# chunkycopter-v2.net
KiCad netlist of a schematic drawn in EAGLE
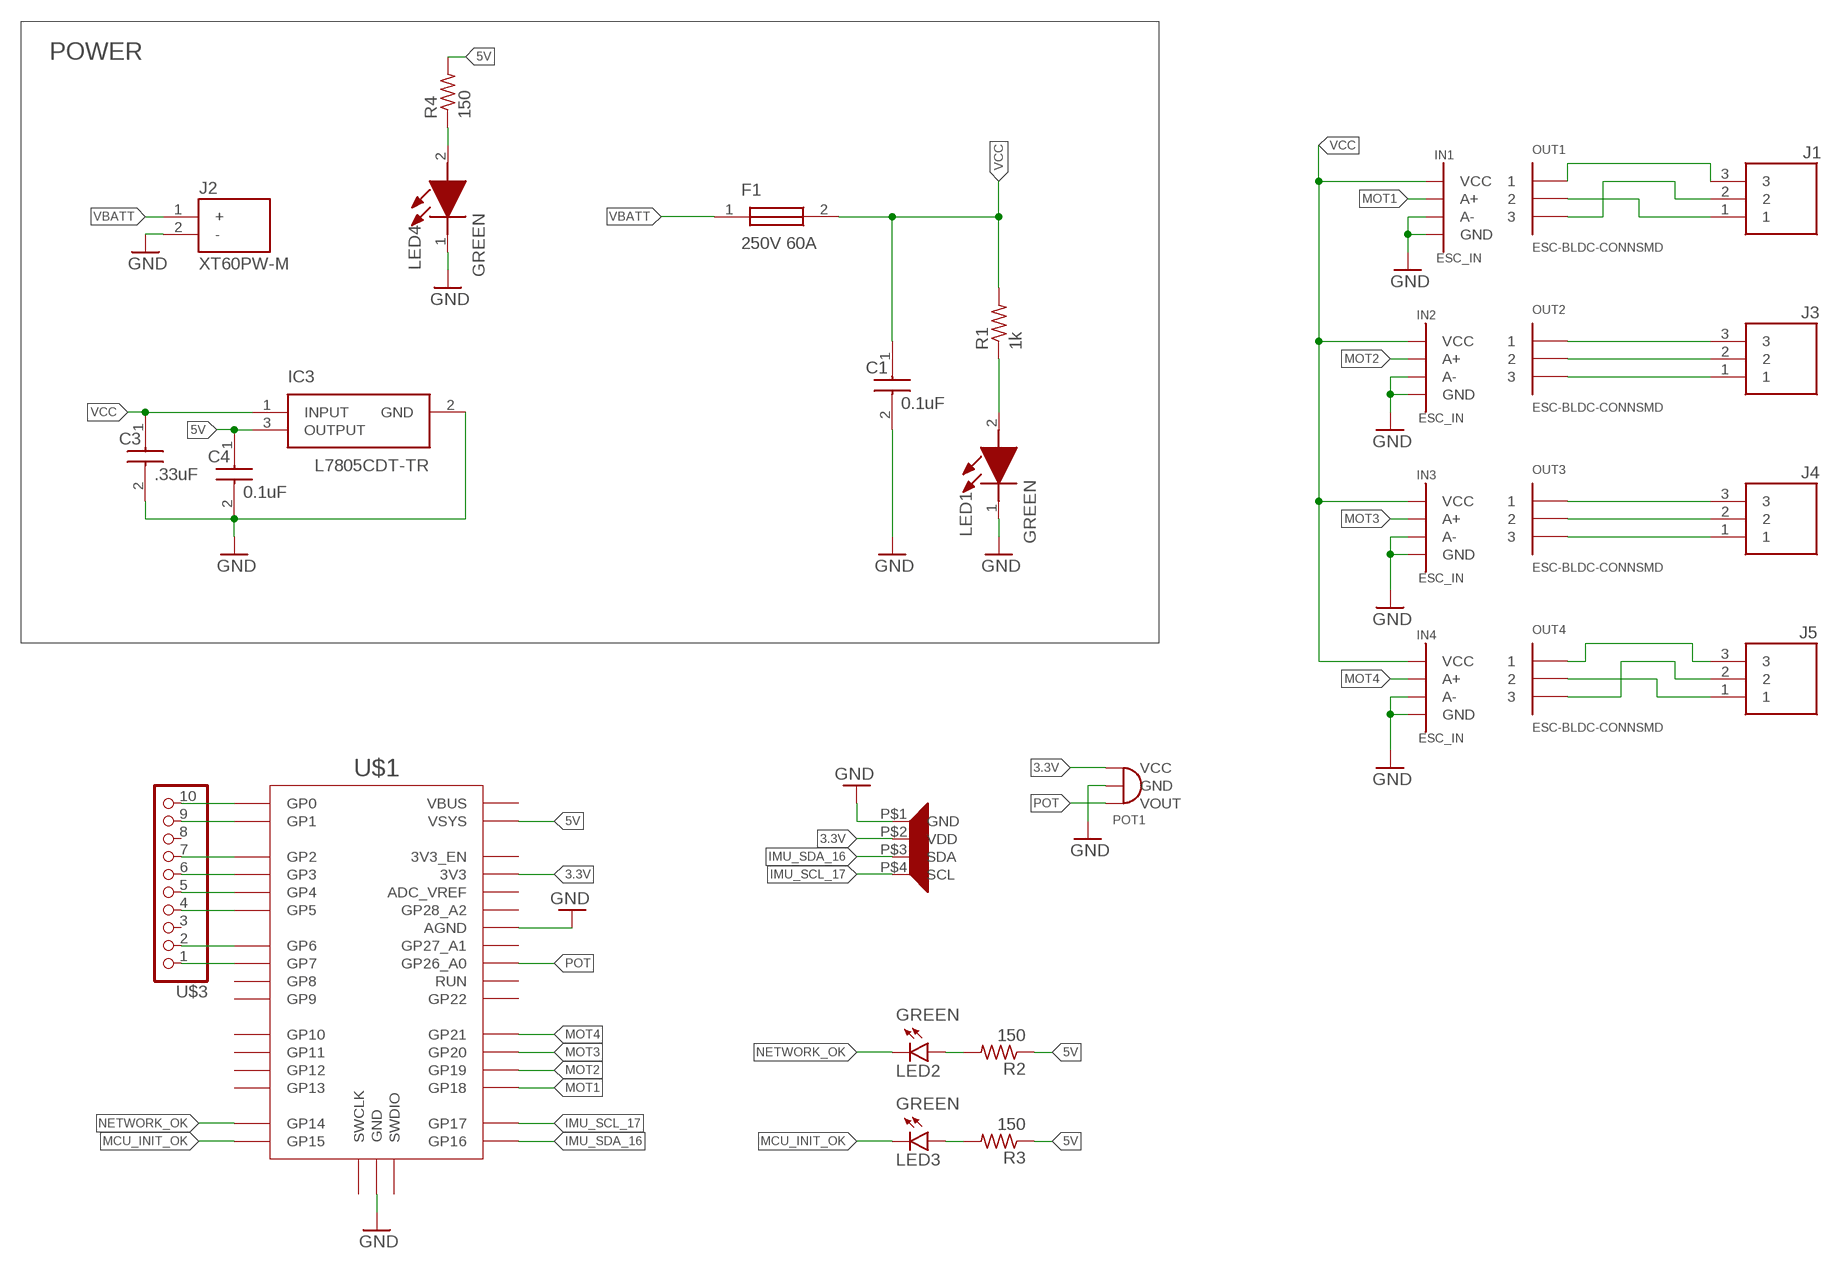
[diagram p0: schematic, sheet 1]

(export (version "E")
  (design (tool "Eeschema 10.0.6"))
  (components
    (comp (ref "C1")
      (value "0.1uF")
      (footprint "eagle-import:C0805")
      (fields
        (field (name "MANUFACTURER_PART_NUMBER") "C0805C104K5RACTU")
        (field (name "MOUSER_PART_NUMBER") "80-C0805C104K5R")
      )
      (libsource (lib "eagle-import") (part "C0805C104K5RACTU"))
    )
    (comp (ref "C3")
      (value ".33uF")
      (footprint "eagle-import:C0805")
      (fields
        (field (name "MANUFACTURER_PART_NUMBER") "C0805C334K5RACTU")
        (field (name "MOUSER_PART_NUMBER") "80-C0805C334K5R")
      )
      (libsource (lib "eagle-import") (part "C0805C334K5RACTU"))
    )
    (comp (ref "C4")
      (value "0.1uF")
      (footprint "eagle-import:C0805")
      (fields
        (field (name "MANUFACTURER_PART_NUMBER") "C0805C104K5RACTU")
        (field (name "MOUSER_PART_NUMBER") "80-C0805C104K5R")
      )
      (libsource (lib "eagle-import") (part "C0805C104K5RACTU"))
    )
    (comp (ref "F1")
      (value "250V 60A")
      (footprint "eagle-import:0456060DRSDE")
      (fields
        (field (name "MANUFACTURER_PART_NUMBER") "0456060.DRSDE")
        (field (name "MOUSER_PART_NUMBER") "576-0456060.DRSDE")
      )
      (libsource (lib "eagle-import") (part "0456060.DRSDE"))
    )
    (comp (ref "IC3")
      (value "L7805CDT-TR")
      (footprint "eagle-import:L7805CDTTR")
      (fields (field (name "MOUSER_PART_NUMBER") "511-L7805CDT-TR"))
      (libsource (lib "eagle-import") (part "L7805CDT-TR"))
    )
    (comp (ref "IN1")
      (value "ESC_IN")
      (footprint "eagle-import:ESC-INPUT")
      (libsource (lib "eagle-import") (part "ESC_IN"))
    )
    (comp (ref "IN2")
      (value "ESC_IN")
      (footprint "eagle-import:ESC-INPUT")
      (libsource (lib "eagle-import") (part "ESC_IN"))
    )
    (comp (ref "IN3")
      (value "ESC_IN")
      (footprint "eagle-import:ESC-INPUT")
      (libsource (lib "eagle-import") (part "ESC_IN"))
    )
    (comp (ref "IN4")
      (value "ESC_IN")
      (footprint "eagle-import:ESC-INPUT")
      (libsource (lib "eagle-import") (part "ESC_IN"))
    )
    (comp (ref "J1")
      (value "MOLEX-CONN-39-30-3037")
      (footprint "eagle-import:39303037")
      (fields
        (field (name "MANUFACTURER_PART_NUMBER") "39-30-3037")
        (field (name "MOUSER_PART_NUMBER") "538-39-30-3037")
      )
      (libsource (lib "eagle-import") (part "MOLEX-CONN-39-30-3037"))
    )
    (comp (ref "J2")
      (value "XT60PW-M")
      (footprint "eagle-import:AMASS_XT60PW-M")
      (fields (field (name "MF") "AMASS"))
      (libsource (lib "eagle-import") (part "XT60PW-M"))
    )
    (comp (ref "J3")
      (value "MOLEX-CONN-39-30-3037")
      (footprint "eagle-import:39303037")
      (fields
        (field (name "MANUFACTURER_PART_NUMBER") "39-30-3037")
        (field (name "MOUSER_PART_NUMBER") "538-39-30-3037")
      )
      (libsource (lib "eagle-import") (part "MOLEX-CONN-39-30-3037"))
    )
    (comp (ref "J4")
      (value "MOLEX-CONN-39-30-3037")
      (footprint "eagle-import:39303037")
      (fields
        (field (name "MANUFACTURER_PART_NUMBER") "39-30-3037")
        (field (name "MOUSER_PART_NUMBER") "538-39-30-3037")
      )
      (libsource (lib "eagle-import") (part "MOLEX-CONN-39-30-3037"))
    )
    (comp (ref "J5")
      (value "MOLEX-CONN-39-30-3037")
      (footprint "eagle-import:39303037")
      (fields
        (field (name "MANUFACTURER_PART_NUMBER") "39-30-3037")
        (field (name "MOUSER_PART_NUMBER") "538-39-30-3037")
      )
      (libsource (lib "eagle-import") (part "MOLEX-CONN-39-30-3037"))
    )
    (comp (ref "LED1")
      (value "GREEN")
      (footprint "eagle-import:SML012ENTT86")
      (fields
        (field (name "MANUFACTURER_PART_NUMBER") "SML012ENTT86")
        (field (name "MOUSER_PART_NUMBER") "755-SML012ENTT86")
      )
      (libsource (lib "eagle-import") (part "SML012ENTT86"))
    )
    (comp (ref "LED2")
      (value "GREEN")
      (footprint "eagle-import:CHIPLED_0603")
      (libsource (lib "eagle-import") (part "LEDCHIPLED_0603"))
    )
    (comp (ref "LED3")
      (value "GREEN")
      (footprint "eagle-import:CHIPLED_0603")
      (libsource (lib "eagle-import") (part "LEDCHIPLED_0603"))
    )
    (comp (ref "LED4")
      (value "GREEN")
      (footprint "eagle-import:SML012ENTT86")
      (fields
        (field (name "MANUFACTURER_PART_NUMBER") "SML012ENTT86")
        (field (name "MOUSER_PART_NUMBER") "755-SML012ENTT86")
      )
      (libsource (lib "eagle-import") (part "SML012ENTT86"))
    )
    (comp (ref "OUT1")
      (value "ESC-BLDC-CONNSMD")
      (footprint "eagle-import:ESC-OUT")
      (libsource (lib "eagle-import") (part "ESC-BLDC-CONNSMD"))
    )
    (comp (ref "OUT2")
      (value "ESC-BLDC-CONNSMD")
      (footprint "eagle-import:ESC-OUT")
      (libsource (lib "eagle-import") (part "ESC-BLDC-CONNSMD"))
    )
    (comp (ref "OUT3")
      (value "ESC-BLDC-CONNSMD")
      (footprint "eagle-import:ESC-OUT")
      (libsource (lib "eagle-import") (part "ESC-BLDC-CONNSMD"))
    )
    (comp (ref "OUT4")
      (value "ESC-BLDC-CONNSMD")
      (footprint "eagle-import:ESC-OUT")
      (libsource (lib "eagle-import") (part "ESC-BLDC-CONNSMD"))
    )
    (comp (ref "POT1")
      (value "POT-CONN")
      (footprint "eagle-import:POT")
      (libsource (lib "eagle-import") (part "POT-CONN"))
    )
    (comp (ref "R1")
      (value "1k")
      (footprint "eagle-import:R0805")
      (libsource (lib "eagle-import") (part "R-US_R0805"))
    )
    (comp (ref "R2")
      (value "150")
      (footprint "eagle-import:R0805")
      (libsource (lib "eagle-import") (part "R-US_R0805"))
    )
    (comp (ref "R3")
      (value "150")
      (footprint "eagle-import:R0805")
      (libsource (lib "eagle-import") (part "R-US_R0805"))
    )
    (comp (ref "R4")
      (value "150")
      (footprint "eagle-import:R0805")
      (libsource (lib "eagle-import") (part "R-US_R0805"))
    )
    (comp (ref "U$1")
      (value "RPI_PICO-TH")
      (footprint "eagle-import:RPI_PICO_TH")
      (libsource (lib "eagle-import") (part "RPI_PICO-TH"))
    )
    (comp (ref "U$2")
      (value "LSM9DS1_IMU")
      (footprint "eagle-import:LSM9DS1_IMU")
      (libsource (lib "eagle-import") (part "LSM9DS1_IMU"))
    )
    (comp (ref "U$3")
      (value "PINHD-1X10")
      (footprint "eagle-import:1X10-BIG")
      (libsource (lib "eagle-import") (part "PINHD-1X10"))
    )
  )
  (nets
    (net (code "1") (name "3.3V") (class "Default")
      (node (ref "POT1") (pin "P_VCC") (pinfunction "VCC_P_VCC") (pintype "bidirectional"))
      (node (ref "U$1") (pin "3V3") (pinfunction "3V3_3V3") (pintype "bidirectional"))
      (node (ref "U$2") (pin "P$2") (pinfunction "VDD_P$2") (pintype "bidirectional"))
    )
    (net (code "2") (name "5V") (class "Default")
      (node (ref "C4") (pin "1") (pinfunction "1_1") (pintype "bidirectional"))
      (node (ref "IC3") (pin "3") (pinfunction "OUTPUT_3") (pintype "bidirectional"))
      (node (ref "R2") (pin "1") (pinfunction "1_1") (pintype "passive"))
      (node (ref "R3") (pin "1") (pinfunction "1_1") (pintype "passive"))
      (node (ref "R4") (pin "2") (pinfunction "2_2") (pintype "passive"))
      (node (ref "U$1") (pin "VSYS") (pinfunction "VSYS_VSYS") (pintype "bidirectional"))
    )
    (net (code "3") (name "GND") (class "Default")
      (node (ref "C1") (pin "2") (pinfunction "2_2") (pintype "bidirectional"))
      (node (ref "C3") (pin "2") (pinfunction "2_2") (pintype "bidirectional"))
      (node (ref "C4") (pin "2") (pinfunction "2_2") (pintype "bidirectional"))
      (node (ref "IC3") (pin "2") (pinfunction "GND_2") (pintype "bidirectional"))
      (node (ref "IN1") (pin "A-") (pinfunction "A-_A-") (pintype "bidirectional"))
      (node (ref "IN1") (pin "GND") (pinfunction "GND_GND") (pintype "bidirectional"))
      (node (ref "IN2") (pin "A-") (pinfunction "A-_A-") (pintype "bidirectional"))
      (node (ref "IN2") (pin "GND") (pinfunction "GND_GND") (pintype "bidirectional"))
      (node (ref "IN3") (pin "A-") (pinfunction "A-_A-") (pintype "bidirectional"))
      (node (ref "IN3") (pin "GND") (pinfunction "GND_GND") (pintype "bidirectional"))
      (node (ref "IN4") (pin "A-") (pinfunction "A-_A-") (pintype "bidirectional"))
      (node (ref "IN4") (pin "GND") (pinfunction "GND_GND") (pintype "bidirectional"))
      (node (ref "J2") (pin "2") (pinfunction "-_2") (pintype "passive"))
      (node (ref "LED1") (pin "1") (pinfunction "K_1") (pintype "bidirectional"))
      (node (ref "LED4") (pin "1") (pinfunction "K_1") (pintype "bidirectional"))
      (node (ref "POT1") (pin "P_GND") (pinfunction "GND_P_GND") (pintype "bidirectional"))
      (node (ref "U$1") (pin "AGND") (pinfunction "AGND_AGND") (pintype "bidirectional"))
      (node (ref "U$1") (pin "GND@1") (pinfunction "GND_GND@1") (pintype "bidirectional"))
      (node (ref "U$1") (pin "GND@2") (pinfunction "GND_GND@2") (pintype "bidirectional"))
      (node (ref "U$1") (pin "GND@3") (pinfunction "GND_GND@3") (pintype "bidirectional"))
      (node (ref "U$1") (pin "GND@4") (pinfunction "GND_GND@4") (pintype "bidirectional"))
      (node (ref "U$1") (pin "GND@5") (pinfunction "GND_GND@5") (pintype "bidirectional"))
      (node (ref "U$1") (pin "GND@6") (pinfunction "GND_GND@6") (pintype "bidirectional"))
      (node (ref "U$1") (pin "GND@7") (pinfunction "GND_GND@7") (pintype "bidirectional"))
      (node (ref "U$1") (pin "GND@8") (pinfunction "GND_GND@8") (pintype "bidirectional"))
      (node (ref "U$2") (pin "P$1") (pinfunction "GND_P$1") (pintype "bidirectional"))
    )
    (net (code "4") (name "IMU_SCL_17") (class "Default")
      (node (ref "U$1") (pin "GP17") (pinfunction "GP17_GP17") (pintype "bidirectional"))
      (node (ref "U$2") (pin "P$4") (pinfunction "SCL_P$4") (pintype "bidirectional"))
    )
    (net (code "5") (name "IMU_SDA_16") (class "Default")
      (node (ref "U$1") (pin "GP16") (pinfunction "GP16_GP16") (pintype "bidirectional"))
      (node (ref "U$2") (pin "P$3") (pinfunction "SDA_P$3") (pintype "bidirectional"))
    )
    (net (code "6") (name "MCU_INIT_OK") (class "Default")
      (node (ref "LED3") (pin "C") (pinfunction "C_C") (pintype "passive"))
      (node (ref "U$1") (pin "GP15") (pinfunction "GP15_GP15") (pintype "bidirectional"))
    )
    (net (code "7") (name "MOT1") (class "Default")
      (node (ref "IN1") (pin "A+") (pinfunction "A+_A+") (pintype "bidirectional"))
      (node (ref "U$1") (pin "GP18") (pinfunction "GP18_GP18") (pintype "bidirectional"))
    )
    (net (code "8") (name "MOT2") (class "Default")
      (node (ref "IN2") (pin "A+") (pinfunction "A+_A+") (pintype "bidirectional"))
      (node (ref "U$1") (pin "GP19") (pinfunction "GP19_GP19") (pintype "bidirectional"))
    )
    (net (code "9") (name "MOT3") (class "Default")
      (node (ref "IN3") (pin "A+") (pinfunction "A+_A+") (pintype "bidirectional"))
      (node (ref "U$1") (pin "GP20") (pinfunction "GP20_GP20") (pintype "bidirectional"))
    )
    (net (code "10") (name "MOT4") (class "Default")
      (node (ref "IN4") (pin "A+") (pinfunction "A+_A+") (pintype "bidirectional"))
      (node (ref "U$1") (pin "GP21") (pinfunction "GP21_GP21") (pintype "bidirectional"))
    )
    (net (code "11") (name "NETWORK_OK") (class "Default")
      (node (ref "LED2") (pin "C") (pinfunction "C_C") (pintype "passive"))
      (node (ref "U$1") (pin "GP14") (pinfunction "GP14_GP14") (pintype "bidirectional"))
    )
    (net (code "12") (name "Net-(J1-Pad1)") (class "Default")
      (node (ref "J1") (pin "1") (pinfunction "1_1") (pintype "bidirectional"))
      (node (ref "OUT1") (pin "2") (pinfunction "2_2") (pintype "bidirectional"))
    )
    (net (code "13") (name "Net-(J1-Pad2)") (class "Default")
      (node (ref "J1") (pin "2") (pinfunction "2_2") (pintype "bidirectional"))
      (node (ref "OUT1") (pin "3") (pinfunction "3_3") (pintype "bidirectional"))
    )
    (net (code "14") (name "Net-(J1-Pad3)") (class "Default")
      (node (ref "J1") (pin "3") (pinfunction "3_3") (pintype "bidirectional"))
      (node (ref "OUT1") (pin "1") (pinfunction "1_1") (pintype "bidirectional"))
    )
    (net (code "15") (name "Net-(J3-Pad1)") (class "Default")
      (node (ref "J3") (pin "1") (pinfunction "1_1") (pintype "bidirectional"))
      (node (ref "OUT2") (pin "3") (pinfunction "3_3") (pintype "bidirectional"))
    )
    (net (code "16") (name "Net-(J3-Pad2)") (class "Default")
      (node (ref "J3") (pin "2") (pinfunction "2_2") (pintype "bidirectional"))
      (node (ref "OUT2") (pin "2") (pinfunction "2_2") (pintype "bidirectional"))
    )
    (net (code "17") (name "Net-(J3-Pad3)") (class "Default")
      (node (ref "J3") (pin "3") (pinfunction "3_3") (pintype "bidirectional"))
      (node (ref "OUT2") (pin "1") (pinfunction "1_1") (pintype "bidirectional"))
    )
    (net (code "18") (name "Net-(J4-Pad1)") (class "Default")
      (node (ref "J4") (pin "1") (pinfunction "1_1") (pintype "bidirectional"))
      (node (ref "OUT3") (pin "3") (pinfunction "3_3") (pintype "bidirectional"))
    )
    (net (code "19") (name "Net-(J4-Pad2)") (class "Default")
      (node (ref "J4") (pin "2") (pinfunction "2_2") (pintype "bidirectional"))
      (node (ref "OUT3") (pin "2") (pinfunction "2_2") (pintype "bidirectional"))
    )
    (net (code "20") (name "Net-(J4-Pad3)") (class "Default")
      (node (ref "J4") (pin "3") (pinfunction "3_3") (pintype "bidirectional"))
      (node (ref "OUT3") (pin "1") (pinfunction "1_1") (pintype "bidirectional"))
    )
    (net (code "21") (name "Net-(J5-Pad1)") (class "Default")
      (node (ref "J5") (pin "1") (pinfunction "1_1") (pintype "bidirectional"))
      (node (ref "OUT4") (pin "2") (pinfunction "2_2") (pintype "bidirectional"))
    )
    (net (code "22") (name "Net-(J5-Pad2)") (class "Default")
      (node (ref "J5") (pin "2") (pinfunction "2_2") (pintype "bidirectional"))
      (node (ref "OUT4") (pin "3") (pinfunction "3_3") (pintype "bidirectional"))
    )
    (net (code "23") (name "Net-(J5-Pad3)") (class "Default")
      (node (ref "J5") (pin "3") (pinfunction "3_3") (pintype "bidirectional"))
      (node (ref "OUT4") (pin "1") (pinfunction "1_1") (pintype "bidirectional"))
    )
    (net (code "24") (name "Net-(LED1-A)") (class "Default")
      (node (ref "LED1") (pin "2") (pinfunction "A_2") (pintype "bidirectional"))
      (node (ref "R1") (pin "1") (pinfunction "1_1") (pintype "passive"))
    )
    (net (code "25") (name "Net-(LED2-PadA)") (class "Default")
      (node (ref "LED2") (pin "A") (pinfunction "A_A") (pintype "passive"))
      (node (ref "R2") (pin "2") (pinfunction "2_2") (pintype "passive"))
    )
    (net (code "26") (name "Net-(LED3-PadA)") (class "Default")
      (node (ref "LED3") (pin "A") (pinfunction "A_A") (pintype "passive"))
      (node (ref "R3") (pin "2") (pinfunction "2_2") (pintype "passive"))
    )
    (net (code "27") (name "Net-(LED4-A)") (class "Default")
      (node (ref "LED4") (pin "2") (pinfunction "A_2") (pintype "bidirectional"))
      (node (ref "R4") (pin "1") (pinfunction "1_1") (pintype "passive"))
    )
    (net (code "28") (name "Net-(U$1-PadGP0)") (class "Default")
      (node (ref "U$1") (pin "GP0") (pinfunction "GP0_GP0") (pintype "bidirectional"))
      (node (ref "U$3") (pin "10") (pinfunction "10_10") (pintype "passive"))
    )
    (net (code "29") (name "Net-(U$1-PadGP1)") (class "Default")
      (node (ref "U$1") (pin "GP1") (pinfunction "GP1_GP1") (pintype "bidirectional"))
      (node (ref "U$3") (pin "9") (pinfunction "9_9") (pintype "passive"))
    )
    (net (code "30") (name "Net-(U$1-PadGP2)") (class "Default")
      (node (ref "U$1") (pin "GP2") (pinfunction "GP2_GP2") (pintype "bidirectional"))
      (node (ref "U$3") (pin "7") (pinfunction "7_7") (pintype "passive"))
    )
    (net (code "31") (name "Net-(U$1-PadGP3)") (class "Default")
      (node (ref "U$1") (pin "GP3") (pinfunction "GP3_GP3") (pintype "bidirectional"))
      (node (ref "U$3") (pin "6") (pinfunction "6_6") (pintype "passive"))
    )
    (net (code "32") (name "Net-(U$1-PadGP4)") (class "Default")
      (node (ref "U$1") (pin "GP4") (pinfunction "GP4_GP4") (pintype "bidirectional"))
      (node (ref "U$3") (pin "5") (pinfunction "5_5") (pintype "passive"))
    )
    (net (code "33") (name "Net-(U$1-PadGP5)") (class "Default")
      (node (ref "U$1") (pin "GP5") (pinfunction "GP5_GP5") (pintype "bidirectional"))
      (node (ref "U$3") (pin "4") (pinfunction "4_4") (pintype "passive"))
    )
    (net (code "34") (name "Net-(U$1-PadGP6)") (class "Default")
      (node (ref "U$1") (pin "GP6") (pinfunction "GP6_GP6") (pintype "bidirectional"))
      (node (ref "U$3") (pin "2") (pinfunction "2_2") (pintype "passive"))
    )
    (net (code "35") (name "Net-(U$1-PadGP7)") (class "Default")
      (node (ref "U$1") (pin "GP7") (pinfunction "GP7_GP7") (pintype "bidirectional"))
      (node (ref "U$3") (pin "1") (pinfunction "1_1") (pintype "passive"))
    )
    (net (code "36") (name "POT") (class "Default")
      (node (ref "POT1") (pin "P_VOUT") (pinfunction "VOUT_P_VOUT") (pintype "bidirectional"))
      (node (ref "U$1") (pin "GP26_A0") (pinfunction "GP26_A0_GP26_A0") (pintype "bidirectional"))
    )
    (net (code "37") (name "VBATT") (class "Default")
      (node (ref "F1") (pin "1") (pinfunction "1_1") (pintype "bidirectional"))
      (node (ref "J2") (pin "1") (pinfunction "+_1") (pintype "passive"))
    )
    (net (code "38") (name "VCC") (class "Default")
      (node (ref "C1") (pin "1") (pinfunction "1_1") (pintype "bidirectional"))
      (node (ref "C3") (pin "1") (pinfunction "1_1") (pintype "bidirectional"))
      (node (ref "F1") (pin "2") (pinfunction "2_2") (pintype "bidirectional"))
      (node (ref "IC3") (pin "1") (pinfunction "INPUT_1") (pintype "bidirectional"))
      (node (ref "IN1") (pin "VCC") (pinfunction "VCC_VCC") (pintype "bidirectional"))
      (node (ref "IN2") (pin "VCC") (pinfunction "VCC_VCC") (pintype "bidirectional"))
      (node (ref "IN3") (pin "VCC") (pinfunction "VCC_VCC") (pintype "bidirectional"))
      (node (ref "IN4") (pin "VCC") (pinfunction "VCC_VCC") (pintype "bidirectional"))
      (node (ref "R1") (pin "2") (pinfunction "2_2") (pintype "passive"))
    )
    (net (code "39") (name "unconnected-(U$1-Pad3V3_EN)") (class "Default")
      (node (ref "U$1") (pin "3V3_EN") (pinfunction "3V3_EN_3V3_EN") (pintype "bidirectional"))
    )
    (net (code "40") (name "unconnected-(U$1-PadADC_VREF)") (class "Default")
      (node (ref "U$1") (pin "ADC_VREF") (pinfunction "ADC_VREF_ADC_VREF") (pintype "bidirectional"))
    )
    (net (code "41") (name "unconnected-(U$1-PadGP8)") (class "Default")
      (node (ref "U$1") (pin "GP8") (pinfunction "GP8_GP8") (pintype "bidirectional"))
    )
    (net (code "42") (name "unconnected-(U$1-PadGP9)") (class "Default")
      (node (ref "U$1") (pin "GP9") (pinfunction "GP9_GP9") (pintype "bidirectional"))
    )
    (net (code "43") (name "unconnected-(U$1-PadGP10)") (class "Default")
      (node (ref "U$1") (pin "GP10") (pinfunction "GP10_GP10") (pintype "bidirectional"))
    )
    (net (code "44") (name "unconnected-(U$1-PadGP11)") (class "Default")
      (node (ref "U$1") (pin "GP11") (pinfunction "GP11_GP11") (pintype "bidirectional"))
    )
    (net (code "45") (name "unconnected-(U$1-PadGP12)") (class "Default")
      (node (ref "U$1") (pin "GP12") (pinfunction "GP12_GP12") (pintype "bidirectional"))
    )
    (net (code "46") (name "unconnected-(U$1-PadGP13)") (class "Default")
      (node (ref "U$1") (pin "GP13") (pinfunction "GP13_GP13") (pintype "bidirectional"))
    )
    (net (code "47") (name "unconnected-(U$1-PadGP22)") (class "Default")
      (node (ref "U$1") (pin "GP22") (pinfunction "GP22_GP22") (pintype "bidirectional"))
    )
    (net (code "48") (name "unconnected-(U$1-PadGP27_A1)") (class "Default")
      (node (ref "U$1") (pin "GP27_A1") (pinfunction "GP27_A1_GP27_A1") (pintype "bidirectional"))
    )
    (net (code "49") (name "unconnected-(U$1-PadGP28_A2)") (class "Default")
      (node (ref "U$1") (pin "GP28_A2") (pinfunction "GP28_A2_GP28_A2") (pintype "bidirectional"))
    )
    (net (code "50") (name "unconnected-(U$1-PadRUN)") (class "Default")
      (node (ref "U$1") (pin "RUN") (pinfunction "RUN_RUN") (pintype "bidirectional"))
    )
    (net (code "51") (name "unconnected-(U$1-PadSWCLK)") (class "Default")
      (node (ref "U$1") (pin "SWCLK") (pinfunction "SWCLK_SWCLK") (pintype "bidirectional"))
    )
    (net (code "52") (name "unconnected-(U$1-PadSWDIO)") (class "Default")
      (node (ref "U$1") (pin "SWDIO") (pinfunction "SWDIO_SWDIO") (pintype "bidirectional"))
    )
    (net (code "53") (name "unconnected-(U$1-PadVBUS)") (class "Default")
      (node (ref "U$1") (pin "VBUS") (pinfunction "VBUS_VBUS") (pintype "bidirectional"))
    )
    (net (code "54") (name "unconnected-(U$3-Pad3)") (class "Default")
      (node (ref "U$3") (pin "3") (pinfunction "3_3") (pintype "passive"))
    )
    (net (code "55") (name "unconnected-(U$3-Pad8)") (class "Default")
      (node (ref "U$3") (pin "8") (pinfunction "8_8") (pintype "passive"))
    )
  )
)
